# Emergency.net
KiCad netlist of a schematic drawn in Altium Designer
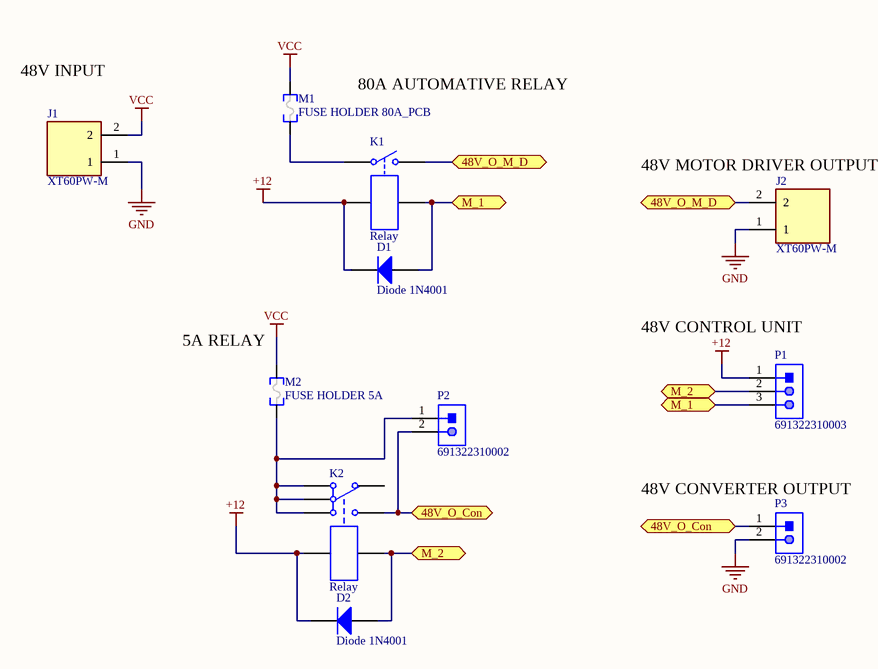
[diagram p0: Emergency.SchDoc]

(export (version "E")
  (design (tool "Eeschema 10.0.6"))
  (components
    (comp (ref "D1")
      (value "Diode 1N4001")
      (footprint "DO-41")
      (description "1 Amp General Purpose Rectifier")
      (fields (field (name "PUBLISHER") "Altium Limited"))
      (libsource (lib "Miscellaneous Devices") (part "Diode 1N4001"))
    )
    (comp (ref "D2")
      (value "Diode 1N4001")
      (footprint "DO-41")
      (description "1 Amp General Purpose Rectifier")
      (fields (field (name "PUBLISHER") "Altium Limited"))
      (libsource (lib "Miscellaneous Devices") (part "Diode 1N4001"))
    )
    (comp (ref "J1")
      (value "XT60PW-M")
      (footprint "AMASS_XT60PW-M")
      (fields (field (name "MF") "AMASS"))
      (libsource (lib "Emergancy") (part "XT60PW-M"))
    )
    (comp (ref "J2")
      (value "XT60PW-M")
      (footprint "AMASS_XT60PW-M")
      (fields (field (name "MF") "AMASS"))
      (libsource (lib "") (part "XT60PW-M_1"))
    )
    (comp (ref "K1")
      (value "Relay")
      (footprint "RL800 12V 80A")
      (description "Mini Röle 12V 80A Güç Rölesi 4 Fişli ÜSTÜN RL800")
      (libsource (lib "Emergancy") (part "RL800 12V 80A"))
    )
    (comp (ref "K2")
      (value "Relay")
      (footprint "TRKP 12V 40A")
      (description "TRKP L-S-Z1/12VDC - RELAY 40A 12VDC FORMC")
      (libsource (lib "Emergancy") (part "TRKP 12V 40A"))
    )
    (comp (ref "M1")
      (value "FUSE HOLDER 80A_PCB")
      (footprint "FUSE HOLDER 80A PCB")
      (description "80A Automative Fuse Holder PCB Baglantisi")
      (libsource (lib "Emergancy") (part "FUSE HOLDER 80A_PCB"))
    )
    (comp (ref "M2")
      (value "FUSE HOLDER 5A")
      (footprint "KEYSTONE 3568")
      (description "5A Automative Fuse Holder Keystone 3568")
      (libsource (lib "Emergancy") (part "FUSE HOLDER 5A"))
    )
    (comp (ref "P1")
      (value "691322310003")
      (footprint "691322310003")
      (description "WR-TBL Serie 322 Horizontal PCB Header, Pluggable, pitch 3.81mm, 3p")
      (fields (field (name "PUBLISHER") "Wurth Elektronik"))
      (libsource (lib "WR-TBL_Pluggable PCB Header") (part "691322310003"))
    )
    (comp (ref "P2")
      (value "691322310002")
      (footprint "691322310002")
      (description "WR-TBL Serie 322 Horizontal PCB Header, Pluggable, pitch 3.81mm, 2p")
      (fields (field (name "PUBLISHER") "Wurth Elektronik"))
      (libsource (lib "WR-TBL_Pluggable PCB Header") (part "691322310002"))
    )
    (comp (ref "P3")
      (value "691322310002")
      (footprint "691322310002")
      (description "WR-TBL Serie 322 Horizontal PCB Header, Pluggable, pitch 3.81mm, 2p")
      (fields (field (name "PUBLISHER") "Wurth Elektronik"))
      (libsource (lib "WR-TBL_Pluggable PCB Header") (part "691322310002"))
    )
  )
  (nets
    (net (code "1") (name "+12") (class "Default")
      (node (ref "D1") (pin "2") (pinfunction "K_2") (pintype "passive"))
      (node (ref "D2") (pin "2") (pinfunction "K_2") (pintype "passive"))
      (node (ref "K1") (pin "3") (pinfunction "85_3") (pintype "passive"))
      (node (ref "K2") (pin "6") (pinfunction "6_6") (pintype "passive"))
      (node (ref "P1") (pin "1") (pinfunction "1_1") (pintype "passive"))
    )
    (net (code "2") (name "/48V_O_Con") (class "Default")
      (node (ref "K2") (pin "5") (pinfunction "5_5") (pintype "passive"))
      (node (ref "P2") (pin "2") (pinfunction "2_2") (pintype "passive"))
      (node (ref "P3") (pin "1") (pinfunction "1_1") (pintype "passive"))
    )
    (net (code "3") (name "/48V_O_M_D") (class "Default")
      (node (ref "J2") (pin "2") (pinfunction "2_2") (pintype "passive"))
      (node (ref "K1") (pin "2") (pinfunction "87_2") (pintype "passive"))
    )
    (net (code "4") (name "/M_1") (class "Default")
      (node (ref "D1") (pin "1") (pinfunction "A_1") (pintype "passive"))
      (node (ref "K1") (pin "4") (pinfunction "86_4") (pintype "passive"))
      (node (ref "P1") (pin "3") (pinfunction "3_3") (pintype "passive"))
    )
    (net (code "5") (name "/M_2") (class "Default")
      (node (ref "D2") (pin "1") (pinfunction "A_1") (pintype "passive"))
      (node (ref "K2") (pin "7") (pinfunction "7_7") (pintype "passive"))
      (node (ref "P1") (pin "2") (pinfunction "2_2") (pintype "passive"))
    )
    (net (code "6") (name "GND") (class "Default")
      (node (ref "J1") (pin "1") (pinfunction "1_1") (pintype "passive"))
      (node (ref "J2") (pin "1") (pinfunction "1_1") (pintype "passive"))
      (node (ref "P3") (pin "2") (pinfunction "2_2") (pintype "passive"))
    )
    (net (code "7") (name "Net-(K1-30)") (class "Default")
      (node (ref "K1") (pin "1") (pinfunction "30_1") (pintype "passive"))
      (node (ref "M1") (pin "1") (pinfunction "1_1") (pintype "passive"))
    )
    (net (code "8") (name "Net-(K2-Pad1)") (class "Default")
      (node (ref "K2") (pin "1") (pinfunction "1_1") (pintype "passive"))
      (node (ref "K2") (pin "2") (pinfunction "2_2") (pintype "passive"))
      (node (ref "K2") (pin "3") (pinfunction "3_3") (pintype "passive"))
      (node (ref "M2") (pin "1") (pinfunction "1_1") (pintype "passive"))
      (node (ref "P2") (pin "1") (pinfunction "1_1") (pintype "passive"))
    )
    (net (code "9") (name "VCC") (class "Default")
      (node (ref "J1") (pin "2") (pinfunction "2_2") (pintype "passive"))
      (node (ref "M1") (pin "2") (pinfunction "2_2") (pintype "passive"))
      (node (ref "M2") (pin "2") (pinfunction "2_2") (pintype "passive"))
    )
    (net (code "10") (name "unconnected-(K2-Pad4)") (class "Default")
      (node (ref "K2") (pin "4") (pinfunction "4_4") (pintype "passive"))
    )
  )
)
